# Estacion_Meteorologica_Sensor_BH1750.net
KiCad netlist of a schematic drawn in Altium Designer
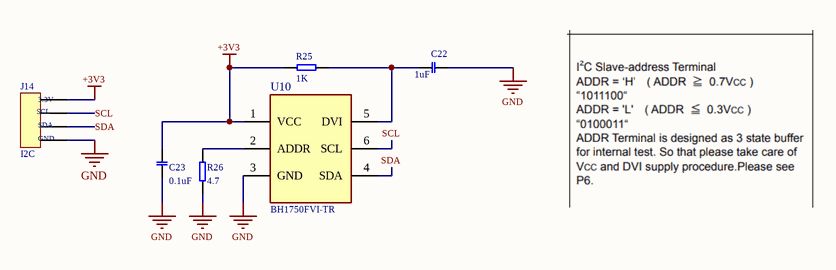
[diagram p0: Estacion_Meteorologica_Sensor_BH1750.SchDoc]

(export (version "E")
  (design (tool "Eeschema 10.0.6"))
  (components
    (comp (ref "C22")
      (value "1uF")
      (footprint "CAPCP1608_0603")
      (description "Capacitor_1uF_0603")
      (libsource (lib "Estacion_Meteorologica_Final") (part "C0603X105J4RACTU"))
    )
    (comp (ref "C23")
      (value "0.1uF")
      (footprint "CAPCP1608_0603")
      (description "Capacitor_0.1uF_0603")
      (libsource (lib "Estacion_Meteorologica_Final") (part "06035C104K4T4A"))
    )
    (comp (ref "J14")
      (value "I2C")
      (footprint "HDR1X4")
      (libsource (lib "Estacion_Meteorologica_Final") (part "Connector_04"))
    )
    (comp (ref "R25")
      (value "1K")
      (footprint "RESC1608_0603")
      (description "Resistencia_1K_0603")
      (libsource (lib "Estacion_Meteorologica_Final") (part "RCA06031K00JNEA"))
    )
    (comp (ref "R26")
      (value "4.7")
      (footprint "RESC1608_0603")
      (description "Resistencia_4.7K_0603")
      (libsource (lib "Estacion_Meteorologica_Final") (part "RCA06034K70FKEA"))
    )
    (comp (ref "U10")
      (value "BH1750FVI-TR")
      (footprint "XDCR_BH1750FVI-TR")
      (description "Optical Sensor Ambient 560nm IÂ²C 6-SMD, Flat Lead Exposed Pad")
      (fields (field (name "MF") "Rohm"))
      (libsource (lib "Estacion_Meteorologica_Final") (part "BH1750FVI-TR"))
    )
  )
  (nets
    (net (code "1") (name "+3V3") (class "Default")
      (node (ref "C23") (pin "2") (pinfunction "2_2") (pintype "passive"))
      (node (ref "J14") (pin "1") (pinfunction "1_1") (pintype "passive"))
      (node (ref "R25") (pin "1") (pinfunction "1_1") (pintype "passive"))
      (node (ref "U10") (pin "1") (pinfunction "VCC_1") (pintype "passive"))
    )
    (net (code "2") (name "/SCL") (class "Default")
      (node (ref "J14") (pin "2") (pinfunction "2_2") (pintype "passive"))
      (node (ref "U10") (pin "6") (pinfunction "SCL_6") (pintype "passive"))
    )
    (net (code "3") (name "/SDA") (class "Default")
      (node (ref "J14") (pin "3") (pinfunction "3_3") (pintype "passive"))
      (node (ref "U10") (pin "4") (pinfunction "SDA_4") (pintype "passive"))
    )
    (net (code "4") (name "GND") (class "Default")
      (node (ref "C22") (pin "2") (pinfunction "2_2") (pintype "passive"))
      (node (ref "C23") (pin "1") (pinfunction "1_1") (pintype "passive"))
      (node (ref "J14") (pin "4") (pinfunction "4_4") (pintype "passive"))
      (node (ref "R26") (pin "1") (pinfunction "1_1") (pintype "passive"))
      (node (ref "U10") (pin "3") (pinfunction "GND_3") (pintype "passive"))
    )
    (net (code "5") (name "Net-(U10-ADDR)") (class "Default")
      (node (ref "R26") (pin "2") (pinfunction "2_2") (pintype "passive"))
      (node (ref "U10") (pin "2") (pinfunction "ADDR_2") (pintype "passive"))
    )
    (net (code "6") (name "Net-(U10-DVI)") (class "Default")
      (node (ref "C22") (pin "1") (pinfunction "1_1") (pintype "passive"))
      (node (ref "R25") (pin "2") (pinfunction "2_2") (pintype "passive"))
      (node (ref "U10") (pin "5") (pinfunction "DVI_5") (pintype "passive"))
    )
  )
)
